# Sheet1.net
KiCad netlist of a schematic drawn in Altium Designer
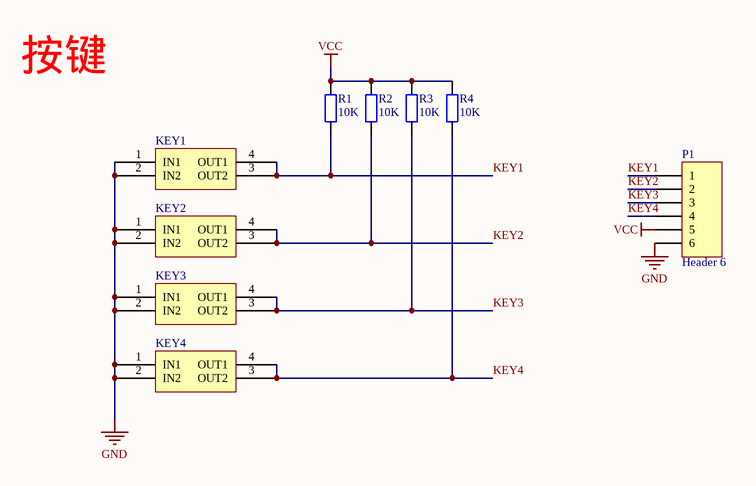
[diagram p0: Sheet1.SchDoc]

(export (version "E")
  (design (tool "Eeschema 10.0.6"))
  (components
    (comp (ref "KEY1") (value "KEY") (footprint "KEY") (libsource (lib "Schlib1") (part "KEY")))
    (comp (ref "KEY2") (value "KEY") (footprint "KEY") (libsource (lib "Schlib1") (part "KEY")))
    (comp (ref "KEY3") (value "KEY") (footprint "KEY") (libsource (lib "Schlib1") (part "KEY")))
    (comp (ref "KEY4") (value "KEY") (footprint "KEY") (libsource (lib "Schlib1") (part "KEY")))
    (comp (ref "P1")
      (value "Header 6")
      (footprint "HDR1X6")
      (description "Header, 6-Pin")
      (fields (field (name "PUBLISHER") "Altium Limited"))
      (libsource (lib "Miscellaneous Connectors") (part "Header 6"))
    )
    (comp (ref "R1")
      (value "10K")
      (footprint "R 0603_M")
      (description "贴片电阻")
      (libsource (lib "01 - 电容-电阻-电感") (part "R"))
    )
    (comp (ref "R2")
      (value "10K")
      (footprint "R 0603_M")
      (description "贴片电阻")
      (libsource (lib "01 - 电容-电阻-电感") (part "R"))
    )
    (comp (ref "R3")
      (value "10K")
      (footprint "R 0603_M")
      (description "贴片电阻")
      (libsource (lib "01 - 电容-电阻-电感") (part "R"))
    )
    (comp (ref "R4")
      (value "10K")
      (footprint "R 0603_M")
      (description "贴片电阻")
      (libsource (lib "01 - 电容-电阻-电感") (part "R"))
    )
  )
  (nets
    (net (code "1") (name "/KEY1") (class "Default")
      (node (ref "KEY1") (pin "3") (pinfunction "OUT2_3") (pintype "passive"))
      (node (ref "KEY1") (pin "4") (pinfunction "OUT1_4") (pintype "passive"))
      (node (ref "P1") (pin "1") (pinfunction "1_1") (pintype "passive"))
      (node (ref "R1") (pin "1") (pinfunction "1_1") (pintype "passive"))
    )
    (net (code "2") (name "/KEY2") (class "Default")
      (node (ref "KEY2") (pin "3") (pinfunction "OUT2_3") (pintype "passive"))
      (node (ref "KEY2") (pin "4") (pinfunction "OUT1_4") (pintype "passive"))
      (node (ref "P1") (pin "2") (pinfunction "2_2") (pintype "passive"))
      (node (ref "R2") (pin "1") (pinfunction "1_1") (pintype "passive"))
    )
    (net (code "3") (name "/KEY3") (class "Default")
      (node (ref "KEY3") (pin "3") (pinfunction "OUT2_3") (pintype "passive"))
      (node (ref "KEY3") (pin "4") (pinfunction "OUT1_4") (pintype "passive"))
      (node (ref "P1") (pin "3") (pinfunction "3_3") (pintype "passive"))
      (node (ref "R3") (pin "1") (pinfunction "1_1") (pintype "passive"))
    )
    (net (code "4") (name "/KEY4") (class "Default")
      (node (ref "KEY4") (pin "3") (pinfunction "OUT2_3") (pintype "passive"))
      (node (ref "KEY4") (pin "4") (pinfunction "OUT1_4") (pintype "passive"))
      (node (ref "P1") (pin "4") (pinfunction "4_4") (pintype "passive"))
      (node (ref "R4") (pin "1") (pinfunction "1_1") (pintype "passive"))
    )
    (net (code "5") (name "GND") (class "Default")
      (node (ref "KEY1") (pin "1") (pinfunction "IN1_1") (pintype "passive"))
      (node (ref "KEY1") (pin "2") (pinfunction "IN2_2") (pintype "passive"))
      (node (ref "KEY2") (pin "1") (pinfunction "IN1_1") (pintype "passive"))
      (node (ref "KEY2") (pin "2") (pinfunction "IN2_2") (pintype "passive"))
      (node (ref "KEY3") (pin "1") (pinfunction "IN1_1") (pintype "passive"))
      (node (ref "KEY3") (pin "2") (pinfunction "IN2_2") (pintype "passive"))
      (node (ref "KEY4") (pin "1") (pinfunction "IN1_1") (pintype "passive"))
      (node (ref "KEY4") (pin "2") (pinfunction "IN2_2") (pintype "passive"))
      (node (ref "P1") (pin "6") (pinfunction "6_6") (pintype "passive"))
    )
    (net (code "6") (name "VCC") (class "Default")
      (node (ref "P1") (pin "5") (pinfunction "5_5") (pintype "passive"))
      (node (ref "R1") (pin "2") (pinfunction "2_2") (pintype "passive"))
      (node (ref "R2") (pin "2") (pinfunction "2_2") (pintype "passive"))
      (node (ref "R3") (pin "2") (pinfunction "2_2") (pintype "passive"))
      (node (ref "R4") (pin "2") (pinfunction "2_2") (pintype "passive"))
    )
  )
)
